# TTFT_3_0_tiny.net
KiCad netlist of a schematic drawn in Altium Designer
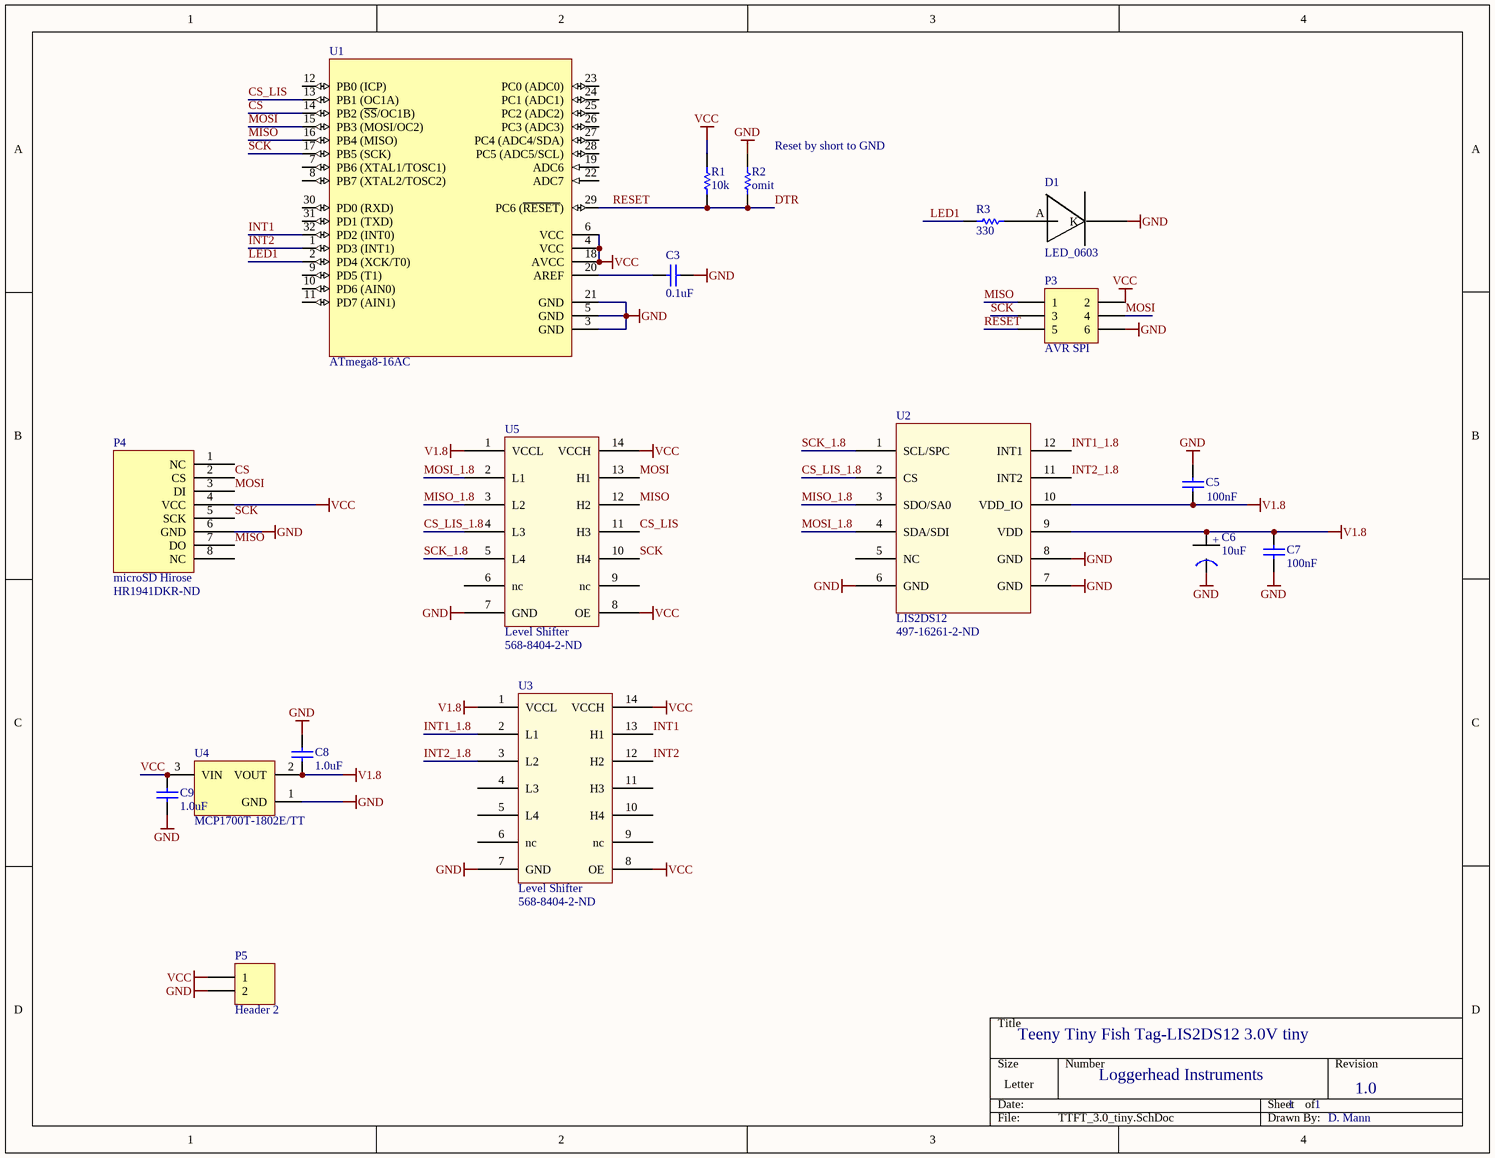
[diagram p0: TTFT_3.0_tiny.SchDoc]

(export (version "E")
  (design (tool "Eeschema 10.0.6"))
  (components
    (comp (ref "C3")
      (value "0.1uF")
      (footprint "0402")
      (description "Ceramic Chip Capacitor - Standard")
      (fields (field (name "PUBLISHER") "Altium Limited"))
      (libsource (lib "KEMET Chip Capacitor") (part "C0402"))
    )
    (comp (ref "C5")
      (value "100nF")
      (footprint "0402")
      (description "Ceramic Chip Capacitor - Standard")
      (fields (field (name "PUBLISHER") "Altium Limited"))
      (libsource (lib "KEMET Chip Capacitor") (part "C0402"))
    )
    (comp (ref "C6") (value "10uF") (footprint "Tant0805") (libsource (lib "Loggerhead") (part "Tant0805")))
    (comp (ref "C7")
      (value "100nF")
      (footprint "0402")
      (description "Ceramic Chip Capacitor - Standard")
      (fields (field (name "PUBLISHER") "Altium Limited"))
      (libsource (lib "KEMET Chip Capacitor") (part "C0402"))
    )
    (comp (ref "C8")
      (value "1.0uF")
      (footprint "0402")
      (description "Ceramic Chip Capacitor - Standard")
      (fields (field (name "PUBLISHER") "Altium Limited"))
      (libsource (lib "KEMET Chip Capacitor") (part "C0402"))
    )
    (comp (ref "C9")
      (value "1.0uF")
      (footprint "0402")
      (description "Ceramic Chip Capacitor - Standard")
      (fields (field (name "PUBLISHER") "Altium Limited"))
      (libsource (lib "KEMET Chip Capacitor") (part "C0402"))
    )
    (comp (ref "D1")
      (value "LED_0603")
      (footprint "Diode0603")
      (libsource (lib "Loggerhead") (part "LED_0603"))
    )
    (comp (ref "P3")
      (value "AVR SPI")
      (footprint "HDR2X3")
      (description "Header, 3-Pin, Dual row")
      (fields (field (name "PUBLISHER") "Altium Limited"))
      (libsource (lib "Miscellaneous Connectors") (part "Header 3X2"))
    )
    (comp (ref "P4")
      (value "microSD Hirose")
      (footprint "DM3D microSD")
      (fields (field (name "SUPPLIER PART NUMBER 1") "HR1941DKR-ND"))
      (libsource (lib "Loggerhead") (part "microSD Hirose"))
    )
    (comp (ref "P5")
      (value "Header 2")
      (footprint "HDR1X2")
      (description "Header, 2-Pin")
      (fields (field (name "PUBLISHER") "Altium Limited"))
      (libsource (lib "Miscellaneous Connectors") (part "Header 2"))
    )
    (comp (ref "R1")
      (value "10k")
      (footprint "3-0603")
      (fields (field (name "PUBLISHER") "Altium Limited"))
      (libsource (lib "Panasonic Resistor") (part "ERJ3RK"))
    )
    (comp (ref "R2")
      (value "omit")
      (footprint "3-0603")
      (fields (field (name "PUBLISHER") "Altium Limited"))
      (libsource (lib "Panasonic Resistor") (part "ERJ3RK"))
    )
    (comp (ref "R3")
      (value "330")
      (footprint "3-0603")
      (fields (field (name "PUBLISHER") "Altium Limited"))
      (libsource (lib "Panasonic Resistor") (part "ERJ3RK"))
    )
    (comp (ref "U1")
      (value "ATmega8-16AC")
      (footprint "32M1-A_M")
      (description "8-Bit AVR Microcontroller with 8K Bytes of In-System Programmable Flash Memory")
      (fields (field (name "PUBLISHER") "Altium Limited"))
      (libsource (lib "Atmel Microcontroller 8-Bit AVR") (part "ATmega8-16AC"))
    )
    (comp (ref "U2")
      (value "LIS2DS12")
      (footprint "LGA-12")
      (fields (field (name "SUPPLIER PART NUMBER 1") "497-16261-2-ND"))
      (libsource (lib "Loggerhead") (part "LIS2DS12"))
    )
    (comp (ref "U3")
      (value "Level Shifter")
      (footprint "DHVQFN14")
      (description "Voltage level translator")
      (fields (field (name "SUPPLIER PART NUMBER 1") "568-8404-2-ND"))
      (libsource (lib "Loggerhead") (part "NTB0104"))
    )
    (comp (ref "U4")
      (value "MCP1700T-1802E/TT")
      (footprint "SOT-23-TT3_N")
      (description "Low Quiescent Current LDO, 3-Pin SOT-23, Extended Temperature, Tape and Reel")
      (fields (field (name "MANUFACTURER") "Microchip"))
      (libsource (lib "Microchip Power Management Line Regulator") (part "MCP1700T-1802E/TT"))
    )
    (comp (ref "U5")
      (value "Level Shifter")
      (footprint "DHVQFN14")
      (description "Voltage level translator")
      (fields (field (name "SUPPLIER PART NUMBER 1") "568-8404-2-ND"))
      (libsource (lib "Loggerhead") (part "NTB0104"))
    )
  )
  (nets
    (net (code "1") (name "/CS") (class "Default")
      (node (ref "P4") (pin "2") (pinfunction "CS_2") (pintype "passive"))
      (node (ref "U1") (pin "14") (pinfunction "PB2_(~{SS}/OC1B)_14") (pintype "bidirectional"))
    )
    (net (code "2") (name "/CS_LIS") (class "Default")
      (node (ref "U1") (pin "13") (pinfunction "PB1_(OC1A)_13") (pintype "bidirectional"))
      (node (ref "U5") (pin "11") (pinfunction "H3_11") (pintype "passive"))
    )
    (net (code "3") (name "/CS_LIS_1.8") (class "Default")
      (node (ref "U2") (pin "2") (pinfunction "CS_2") (pintype "passive"))
      (node (ref "U5") (pin "4") (pinfunction "L3_4") (pintype "passive"))
    )
    (net (code "4") (name "/DTR") (class "Default")
      (node (ref "P3") (pin "5") (pinfunction "5_5") (pintype "passive"))
      (node (ref "R1") (pin "1") (pinfunction "1_1") (pintype "passive"))
      (node (ref "R2") (pin "1") (pinfunction "1_1") (pintype "passive"))
      (node (ref "U1") (pin "29") (pinfunction "PC6_(~{RESET})_29") (pintype "bidirectional"))
    )
    (net (code "5") (name "/INT1") (class "Default")
      (node (ref "U1") (pin "32") (pinfunction "PD2_(INT0)_32") (pintype "bidirectional"))
      (node (ref "U3") (pin "13") (pinfunction "H1_13") (pintype "passive"))
    )
    (net (code "6") (name "/INT1_1.8") (class "Default")
      (node (ref "U2") (pin "12") (pinfunction "INT1_12") (pintype "passive"))
      (node (ref "U3") (pin "2") (pinfunction "L1_2") (pintype "passive"))
    )
    (net (code "7") (name "/INT2") (class "Default")
      (node (ref "U1") (pin "1") (pinfunction "PD3_(INT1)_1") (pintype "bidirectional"))
      (node (ref "U3") (pin "12") (pinfunction "H2_12") (pintype "passive"))
    )
    (net (code "8") (name "/INT2_1.8") (class "Default")
      (node (ref "U2") (pin "11") (pinfunction "INT2_11") (pintype "passive"))
      (node (ref "U3") (pin "3") (pinfunction "L2_3") (pintype "passive"))
    )
    (net (code "9") (name "/LED1") (class "Default")
      (node (ref "R3") (pin "1") (pinfunction "1_1") (pintype "passive"))
      (node (ref "U1") (pin "2") (pinfunction "PD4_(XCK/T0)_2") (pintype "bidirectional"))
    )
    (net (code "10") (name "/MISO") (class "Default")
      (node (ref "P3") (pin "1") (pinfunction "1_1") (pintype "passive"))
      (node (ref "P4") (pin "7") (pinfunction "DO_7") (pintype "passive"))
      (node (ref "U1") (pin "16") (pinfunction "PB4_(MISO)_16") (pintype "bidirectional"))
      (node (ref "U5") (pin "12") (pinfunction "H2_12") (pintype "passive"))
    )
    (net (code "11") (name "/MISO_1.8") (class "Default")
      (node (ref "U2") (pin "3") (pinfunction "SDO/SA0_3") (pintype "passive"))
      (node (ref "U5") (pin "3") (pinfunction "L2_3") (pintype "passive"))
    )
    (net (code "12") (name "/MOSI") (class "Default")
      (node (ref "P3") (pin "4") (pinfunction "4_4") (pintype "passive"))
      (node (ref "P4") (pin "3") (pinfunction "DI_3") (pintype "passive"))
      (node (ref "U1") (pin "15") (pinfunction "PB3_(MOSI/OC2)_15") (pintype "bidirectional"))
      (node (ref "U5") (pin "13") (pinfunction "H1_13") (pintype "passive"))
    )
    (net (code "13") (name "/MOSI_1.8") (class "Default")
      (node (ref "U2") (pin "4") (pinfunction "SDA/SDI_4") (pintype "passive"))
      (node (ref "U5") (pin "2") (pinfunction "L1_2") (pintype "passive"))
    )
    (net (code "14") (name "/SCK") (class "Default")
      (node (ref "P3") (pin "3") (pinfunction "3_3") (pintype "passive"))
      (node (ref "P4") (pin "5") (pinfunction "SCK_5") (pintype "passive"))
      (node (ref "U1") (pin "17") (pinfunction "PB5_(SCK)_17") (pintype "bidirectional"))
      (node (ref "U5") (pin "10") (pinfunction "H4_10") (pintype "passive"))
    )
    (net (code "15") (name "/SCK_1.8") (class "Default")
      (node (ref "U2") (pin "1") (pinfunction "SCL/SPC_1") (pintype "passive"))
      (node (ref "U5") (pin "5") (pinfunction "L4_5") (pintype "passive"))
    )
    (net (code "16") (name "GND") (class "Default")
      (node (ref "C3") (pin "2") (pinfunction "2_2") (pintype "passive"))
      (node (ref "C5") (pin "2") (pinfunction "2_2") (pintype "passive"))
      (node (ref "C6") (pin "1") (pinfunction "GND_1") (pintype "passive"))
      (node (ref "C7") (pin "2") (pinfunction "2_2") (pintype "passive"))
      (node (ref "C8") (pin "2") (pinfunction "2_2") (pintype "passive"))
      (node (ref "C9") (pin "2") (pinfunction "2_2") (pintype "passive"))
      (node (ref "D1") (pin "K") (pinfunction "K_K") (pintype "passive"))
      (node (ref "P3") (pin "6") (pinfunction "6_6") (pintype "passive"))
      (node (ref "P4") (pin "6") (pinfunction "GND_6") (pintype "passive"))
      (node (ref "P5") (pin "2") (pinfunction "2_2") (pintype "passive"))
      (node (ref "R2") (pin "2") (pinfunction "2_2") (pintype "passive"))
      (node (ref "U1") (pin "21") (pinfunction "GND_21") (pintype "power_in"))
      (node (ref "U1") (pin "3") (pinfunction "GND_3") (pintype "power_in"))
      (node (ref "U1") (pin "5") (pinfunction "GND_5") (pintype "power_in"))
      (node (ref "U2") (pin "6") (pinfunction "GND_6") (pintype "passive"))
      (node (ref "U2") (pin "7") (pinfunction "GND_7") (pintype "passive"))
      (node (ref "U2") (pin "8") (pinfunction "GND_8") (pintype "passive"))
      (node (ref "U3") (pin "7") (pinfunction "GND_7") (pintype "passive"))
      (node (ref "U4") (pin "1") (pinfunction "GND_1") (pintype "power_in"))
      (node (ref "U5") (pin "7") (pinfunction "GND_7") (pintype "passive"))
    )
    (net (code "17") (name "Net-(D1-PadA)") (class "Default")
      (node (ref "D1") (pin "A") (pinfunction "A_A") (pintype "passive"))
      (node (ref "R3") (pin "2") (pinfunction "2_2") (pintype "passive"))
    )
    (net (code "18") (name "Net-(U1-AREF)") (class "Default")
      (node (ref "C3") (pin "1") (pinfunction "1_1") (pintype "passive"))
      (node (ref "U1") (pin "20") (pinfunction "AREF_20") (pintype "passive"))
    )
    (net (code "19") (name "V1.8") (class "Default")
      (node (ref "C5") (pin "1") (pinfunction "1_1") (pintype "passive"))
      (node (ref "C6") (pin "2") (pinfunction "+_2") (pintype "passive"))
      (node (ref "C7") (pin "1") (pinfunction "1_1") (pintype "passive"))
      (node (ref "C8") (pin "1") (pinfunction "1_1") (pintype "passive"))
      (node (ref "U2") (pin "10") (pinfunction "VDD_IO_10") (pintype "passive"))
      (node (ref "U2") (pin "9") (pinfunction "VDD_9") (pintype "passive"))
      (node (ref "U3") (pin "1") (pinfunction "VCCL_1") (pintype "passive"))
      (node (ref "U4") (pin "2") (pinfunction "VOUT_2") (pintype "power_in"))
      (node (ref "U5") (pin "1") (pinfunction "VCCL_1") (pintype "passive"))
    )
    (net (code "20") (name "VCC") (class "Default")
      (node (ref "C9") (pin "1") (pinfunction "1_1") (pintype "passive"))
      (node (ref "P3") (pin "2") (pinfunction "2_2") (pintype "passive"))
      (node (ref "P4") (pin "4") (pinfunction "VCC_4") (pintype "passive"))
      (node (ref "P5") (pin "1") (pinfunction "1_1") (pintype "passive"))
      (node (ref "R1") (pin "2") (pinfunction "2_2") (pintype "passive"))
      (node (ref "U1") (pin "18") (pinfunction "AVCC_18") (pintype "power_in"))
      (node (ref "U1") (pin "4") (pinfunction "VCC_4") (pintype "power_in"))
      (node (ref "U1") (pin "6") (pinfunction "VCC_6") (pintype "power_in"))
      (node (ref "U3") (pin "14") (pinfunction "VCCH_14") (pintype "passive"))
      (node (ref "U3") (pin "8") (pinfunction "OE_8") (pintype "passive"))
      (node (ref "U4") (pin "3") (pinfunction "VIN_3") (pintype "power_in"))
      (node (ref "U5") (pin "14") (pinfunction "VCCH_14") (pintype "passive"))
      (node (ref "U5") (pin "8") (pinfunction "OE_8") (pintype "passive"))
    )
    (net (code "21") (name "unconnected-(P4-NC-Pad1)") (class "Default")
      (node (ref "P4") (pin "1") (pinfunction "NC_1") (pintype "passive"))
    )
    (net (code "22") (name "unconnected-(P4-NC-Pad8)") (class "Default")
      (node (ref "P4") (pin "8") (pinfunction "NC_8") (pintype "passive"))
    )
    (net (code "23") (name "unconnected-(U1-ADC6-Pad19)") (class "Default")
      (node (ref "U1") (pin "19") (pinfunction "ADC6_19") (pintype "input"))
    )
    (net (code "24") (name "unconnected-(U1-ADC7-Pad22)") (class "Default")
      (node (ref "U1") (pin "22") (pinfunction "ADC7_22") (pintype "input"))
    )
    (net (code "25") (name "unconnected-(U1-PB0_(ICP)-Pad12)") (class "Default")
      (node (ref "U1") (pin "12") (pinfunction "PB0_(ICP)_12") (pintype "bidirectional"))
    )
    (net (code "26") (name "unconnected-(U1-PB6_(XTAL1{slash}TOSC1)-Pad7)") (class "Default")
      (node (ref "U1") (pin "7") (pinfunction "PB6_(XTAL1/TOSC1)_7") (pintype "bidirectional"))
    )
    (net (code "27") (name "unconnected-(U1-PB7_(XTAL2{slash}TOSC2)-Pad8)") (class "Default")
      (node (ref "U1") (pin "8") (pinfunction "PB7_(XTAL2/TOSC2)_8") (pintype "bidirectional"))
    )
    (net (code "28") (name "unconnected-(U1-PC0_(ADC0)-Pad23)") (class "Default")
      (node (ref "U1") (pin "23") (pinfunction "PC0_(ADC0)_23") (pintype "bidirectional"))
    )
    (net (code "29") (name "unconnected-(U1-PC1_(ADC1)-Pad24)") (class "Default")
      (node (ref "U1") (pin "24") (pinfunction "PC1_(ADC1)_24") (pintype "bidirectional"))
    )
    (net (code "30") (name "unconnected-(U1-PC2_(ADC2)-Pad25)") (class "Default")
      (node (ref "U1") (pin "25") (pinfunction "PC2_(ADC2)_25") (pintype "bidirectional"))
    )
    (net (code "31") (name "unconnected-(U1-PC3_(ADC3)-Pad26)") (class "Default")
      (node (ref "U1") (pin "26") (pinfunction "PC3_(ADC3)_26") (pintype "bidirectional"))
    )
    (net (code "32") (name "unconnected-(U1-PC4_(ADC4{slash}SDA)-Pad27)") (class "Default")
      (node (ref "U1") (pin "27") (pinfunction "PC4_(ADC4/SDA)_27") (pintype "bidirectional"))
    )
    (net (code "33") (name "unconnected-(U1-PC5_(ADC5{slash}SCL)-Pad28)") (class "Default")
      (node (ref "U1") (pin "28") (pinfunction "PC5_(ADC5/SCL)_28") (pintype "bidirectional"))
    )
    (net (code "34") (name "unconnected-(U1-PD0_(RXD)-Pad30)") (class "Default")
      (node (ref "U1") (pin "30") (pinfunction "PD0_(RXD)_30") (pintype "bidirectional"))
    )
    (net (code "35") (name "unconnected-(U1-PD1_(TXD)-Pad31)") (class "Default")
      (node (ref "U1") (pin "31") (pinfunction "PD1_(TXD)_31") (pintype "bidirectional"))
    )
    (net (code "36") (name "unconnected-(U1-PD5_(T1)-Pad9)") (class "Default")
      (node (ref "U1") (pin "9") (pinfunction "PD5_(T1)_9") (pintype "bidirectional"))
    )
    (net (code "37") (name "unconnected-(U1-PD6_(AIN0)-Pad10)") (class "Default")
      (node (ref "U1") (pin "10") (pinfunction "PD6_(AIN0)_10") (pintype "bidirectional"))
    )
    (net (code "38") (name "unconnected-(U1-PD7_(AIN1)-Pad11)") (class "Default")
      (node (ref "U1") (pin "11") (pinfunction "PD7_(AIN1)_11") (pintype "bidirectional"))
    )
    (net (code "39") (name "unconnected-(U2-NC-Pad5)") (class "Default")
      (node (ref "U2") (pin "5") (pinfunction "NC_5") (pintype "passive"))
    )
    (net (code "40") (name "unconnected-(U3-H3-Pad11)") (class "Default")
      (node (ref "U3") (pin "11") (pinfunction "H3_11") (pintype "passive"))
    )
    (net (code "41") (name "unconnected-(U3-H4-Pad10)") (class "Default")
      (node (ref "U3") (pin "10") (pinfunction "H4_10") (pintype "passive"))
    )
    (net (code "42") (name "unconnected-(U3-L3-Pad4)") (class "Default")
      (node (ref "U3") (pin "4") (pinfunction "L3_4") (pintype "passive"))
    )
    (net (code "43") (name "unconnected-(U3-L4-Pad5)") (class "Default")
      (node (ref "U3") (pin "5") (pinfunction "L4_5") (pintype "passive"))
    )
    (net (code "44") (name "unconnected-(U3-nc-Pad6)") (class "Default")
      (node (ref "U3") (pin "6") (pinfunction "nc_6") (pintype "passive"))
    )
    (net (code "45") (name "unconnected-(U3-nc-Pad9)") (class "Default")
      (node (ref "U3") (pin "9") (pinfunction "nc_9") (pintype "passive"))
    )
    (net (code "46") (name "unconnected-(U5-nc-Pad6)") (class "Default")
      (node (ref "U5") (pin "6") (pinfunction "nc_6") (pintype "passive"))
    )
    (net (code "47") (name "unconnected-(U5-nc-Pad9)") (class "Default")
      (node (ref "U5") (pin "9") (pinfunction "nc_9") (pintype "passive"))
    )
  )
)
